# v1-landshark-handheld-controller.net
KiCad netlist of a schematic drawn in EAGLE
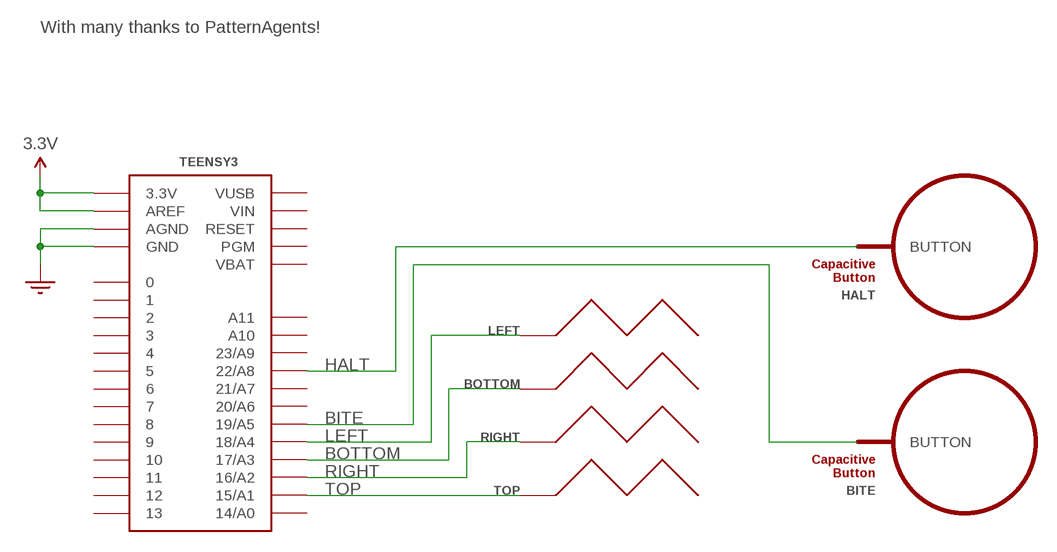
[diagram p0: schematic, sheet 1]

(export (version "E")
  (design (tool "Eeschema 10.0.6"))
  (components
    (comp (ref "BITE")
      (value "BUTTON_PASSIVE12MM")
      (footprint "eagle-import:BUTTON_PASSIVE_12MM")
      (libsource (lib "eagle-import") (part "BUTTON_PASSIVE12MM"))
    )
    (comp (ref "BOTTOM")
      (value "SLIDER_PASSIVE_1SEG")
      (footprint "eagle-import:SLIDER_PASSIVE_1SEG_12MM")
      (libsource (lib "eagle-import") (part "SLIDER_PASSIVE_1SEG"))
    )
    (comp (ref "HALT")
      (value "BUTTON_PASSIVE12MM")
      (footprint "eagle-import:BUTTON_PASSIVE_12MM")
      (libsource (lib "eagle-import") (part "BUTTON_PASSIVE12MM"))
    )
    (comp (ref "LEFT")
      (value "SLIDER_PASSIVE_1SEG")
      (footprint "eagle-import:SLIDER_PASSIVE_1SEG_12MM")
      (libsource (lib "eagle-import") (part "SLIDER_PASSIVE_1SEG"))
    )
    (comp (ref "RIGHT")
      (value "SLIDER_PASSIVE_1SEG")
      (footprint "eagle-import:SLIDER_PASSIVE_1SEG_12MM")
      (libsource (lib "eagle-import") (part "SLIDER_PASSIVE_1SEG"))
    )
    (comp (ref "TEENSY3")
      (value "TEENSY_3.0+4")
      (footprint "eagle-import:TEENSY_3.0+4")
      (libsource (lib "eagle-import") (part "TEENSY_3.0+4"))
    )
    (comp (ref "TOP")
      (value "SLIDER_PASSIVE_1SEG")
      (footprint "eagle-import:SLIDER_PASSIVE_1SEG_12MM")
      (libsource (lib "eagle-import") (part "SLIDER_PASSIVE_1SEG"))
    )
  )
  (nets
    (net (code "1") (name "/BITE") (class "Default")
      (node (ref "BITE") (pin "BUTTON") (pinfunction "BUTTON_BUTTON") (pintype "passive"))
      (node (ref "TEENSY3") (pin "19/A5") (pinfunction "19/A5_19/A5") (pintype "bidirectional"))
    )
    (net (code "2") (name "/BOTTOM") (class "Default")
      (node (ref "BOTTOM") (pin "P$1") (pinfunction "SL1_P$1") (pintype "passive"))
      (node (ref "TEENSY3") (pin "17/A3") (pinfunction "17/A3_17/A3") (pintype "bidirectional"))
    )
    (net (code "3") (name "/HALT") (class "Default")
      (node (ref "HALT") (pin "BUTTON") (pinfunction "BUTTON_BUTTON") (pintype "passive"))
      (node (ref "TEENSY3") (pin "22/A8") (pinfunction "22/A8_22/A8") (pintype "bidirectional"))
    )
    (net (code "4") (name "/LEFT") (class "Default")
      (node (ref "LEFT") (pin "P$1") (pinfunction "SL1_P$1") (pintype "passive"))
      (node (ref "TEENSY3") (pin "18/A4") (pinfunction "18/A4_18/A4") (pintype "bidirectional"))
    )
    (net (code "5") (name "/RIGHT") (class "Default")
      (node (ref "RIGHT") (pin "P$1") (pinfunction "SL1_P$1") (pintype "passive"))
      (node (ref "TEENSY3") (pin "16/A2") (pinfunction "16/A2_16/A2") (pintype "bidirectional"))
    )
    (net (code "6") (name "/TOP") (class "Default")
      (node (ref "TEENSY3") (pin "15/A1") (pinfunction "15/A1_15/A1") (pintype "bidirectional"))
      (node (ref "TOP") (pin "P$1") (pinfunction "SL1_P$1") (pintype "passive"))
    )
    (net (code "7") (name "/VBAT") (class "Default")
      (node (ref "TEENSY3") (pin "VBAT") (pinfunction "VBAT_VBAT") (pintype "power_in"))
    )
    (net (code "8") (name "/VIN") (class "Default")
      (node (ref "TEENSY3") (pin "VIN") (pinfunction "VIN_VIN") (pintype "power_in"))
    )
    (net (code "9") (name "/VUSB") (class "Default")
      (node (ref "TEENSY3") (pin "VUSB") (pinfunction "VUSB_VUSB") (pintype "power_in"))
    )
    (net (code "10") (name "3.3V") (class "Default")
      (node (ref "TEENSY3") (pin "3.3V") (pinfunction "3.3V_3.3V") (pintype "power_in"))
      (node (ref "TEENSY3") (pin "3.3V1") (pinfunction "3.3V_3.3V1") (pintype "power_in"))
      (node (ref "TEENSY3") (pin "AREF") (pinfunction "AREF_AREF") (pintype "power_in"))
    )
    (net (code "11") (name "GND") (class "Default")
      (node (ref "TEENSY3") (pin "AGND") (pinfunction "AGND_AGND") (pintype "power_in"))
      (node (ref "TEENSY3") (pin "GND") (pinfunction "GND_GND") (pintype "power_in"))
      (node (ref "TEENSY3") (pin "GND1") (pinfunction "GND_GND1") (pintype "power_in"))
    )
    (net (code "12") (name "unconnected-(TEENSY3-Pad0)") (class "Default")
      (node (ref "TEENSY3") (pin "0") (pinfunction "0_0") (pintype "bidirectional"))
    )
    (net (code "13") (name "unconnected-(TEENSY3-Pad1)") (class "Default")
      (node (ref "TEENSY3") (pin "1") (pinfunction "1_1") (pintype "bidirectional"))
    )
    (net (code "14") (name "unconnected-(TEENSY3-Pad2)") (class "Default")
      (node (ref "TEENSY3") (pin "2") (pinfunction "2_2") (pintype "bidirectional"))
    )
    (net (code "15") (name "unconnected-(TEENSY3-Pad3)") (class "Default")
      (node (ref "TEENSY3") (pin "3") (pinfunction "3_3") (pintype "bidirectional"))
    )
    (net (code "16") (name "unconnected-(TEENSY3-Pad4)") (class "Default")
      (node (ref "TEENSY3") (pin "4") (pinfunction "4_4") (pintype "bidirectional"))
    )
    (net (code "17") (name "unconnected-(TEENSY3-Pad5)") (class "Default")
      (node (ref "TEENSY3") (pin "5") (pinfunction "5_5") (pintype "bidirectional"))
    )
    (net (code "18") (name "unconnected-(TEENSY3-Pad6)") (class "Default")
      (node (ref "TEENSY3") (pin "6") (pinfunction "6_6") (pintype "bidirectional"))
    )
    (net (code "19") (name "unconnected-(TEENSY3-Pad7)") (class "Default")
      (node (ref "TEENSY3") (pin "7") (pinfunction "7_7") (pintype "bidirectional"))
    )
    (net (code "20") (name "unconnected-(TEENSY3-Pad8)") (class "Default")
      (node (ref "TEENSY3") (pin "8") (pinfunction "8_8") (pintype "bidirectional"))
    )
    (net (code "21") (name "unconnected-(TEENSY3-Pad9)") (class "Default")
      (node (ref "TEENSY3") (pin "9") (pinfunction "9_9") (pintype "bidirectional"))
    )
    (net (code "22") (name "unconnected-(TEENSY3-Pad10)") (class "Default")
      (node (ref "TEENSY3") (pin "10") (pinfunction "10_10") (pintype "bidirectional"))
    )
    (net (code "23") (name "unconnected-(TEENSY3-Pad11)") (class "Default")
      (node (ref "TEENSY3") (pin "11") (pinfunction "11_11") (pintype "bidirectional"))
    )
    (net (code "24") (name "unconnected-(TEENSY3-Pad12)") (class "Default")
      (node (ref "TEENSY3") (pin "12") (pinfunction "12_12") (pintype "bidirectional"))
    )
    (net (code "25") (name "unconnected-(TEENSY3-Pad13)") (class "Default")
      (node (ref "TEENSY3") (pin "13") (pinfunction "13_13") (pintype "bidirectional"))
    )
    (net (code "26") (name "unconnected-(TEENSY3-Pad14{slash}A0)") (class "Default")
      (node (ref "TEENSY3") (pin "14/A0") (pinfunction "14/A0_14/A0") (pintype "bidirectional"))
    )
    (net (code "27") (name "unconnected-(TEENSY3-Pad20{slash}A6)") (class "Default")
      (node (ref "TEENSY3") (pin "20/A6") (pinfunction "20/A6_20/A6") (pintype "bidirectional"))
    )
    (net (code "28") (name "unconnected-(TEENSY3-Pad21{slash}A7)") (class "Default")
      (node (ref "TEENSY3") (pin "21/A7") (pinfunction "21/A7_21/A7") (pintype "bidirectional"))
    )
    (net (code "29") (name "unconnected-(TEENSY3-Pad23{slash}A9)") (class "Default")
      (node (ref "TEENSY3") (pin "23/A9") (pinfunction "23/A9_23/A9") (pintype "bidirectional"))
    )
    (net (code "30") (name "unconnected-(TEENSY3-PadA10)") (class "Default")
      (node (ref "TEENSY3") (pin "A10") (pinfunction "A10_A10") (pintype "bidirectional"))
    )
    (net (code "31") (name "unconnected-(TEENSY3-PadA11)") (class "Default")
      (node (ref "TEENSY3") (pin "A11") (pinfunction "A11_A11") (pintype "bidirectional"))
    )
    (net (code "32") (name "unconnected-(TEENSY3-PadPGM)") (class "Default")
      (node (ref "TEENSY3") (pin "PGM") (pinfunction "PGM_PGM") (pintype "bidirectional"))
    )
    (net (code "33") (name "unconnected-(TEENSY3-PadRESET)") (class "Default")
      (node (ref "TEENSY3") (pin "RESET") (pinfunction "RESET_RESET") (pintype "bidirectional"))
    )
  )
)
